# Sheet2.net
KiCad netlist of a schematic drawn in Altium Designer
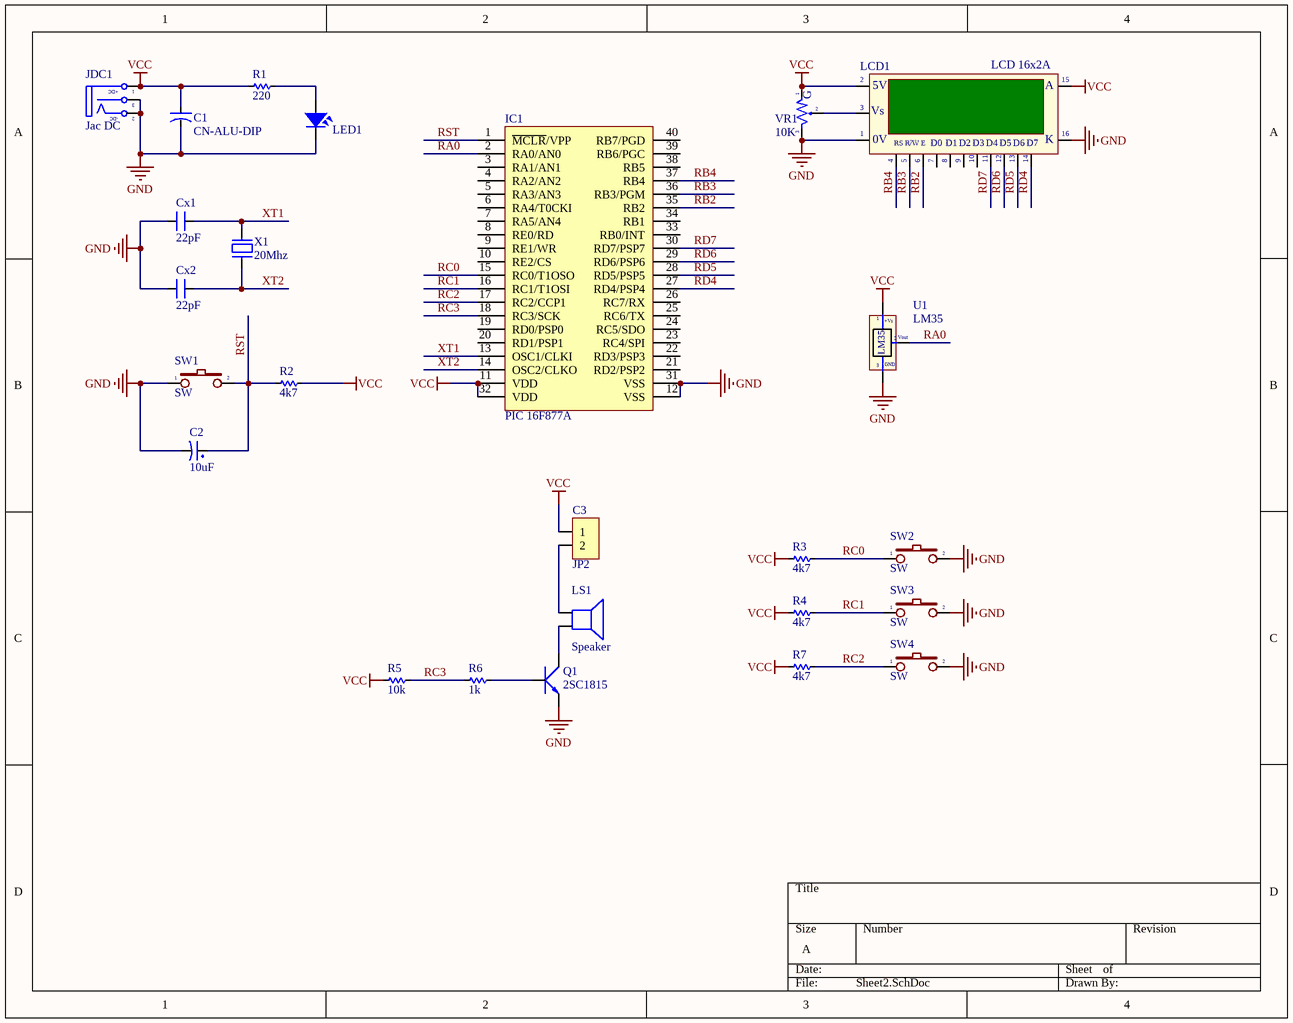
[diagram p0: Sheet2.SchDoc]

(export (version "E")
  (design (tool "Eeschema 10.0.6"))
  (components
    (comp (ref "C1")
      (value "CN-ALU-DIP")
      (footprint "CA-ALU-8")
      (description "Capacitor (Semiconductor SIM Model)")
      (fields (field (name "PUBLISHER") "Altium Limited"))
      (libsource (lib "LIBRARY") (part "CN-ALU-DIP"))
    )
    (comp (ref "C2")
      (value "10uF")
      (footprint "CP1/2")
      (description "Cap P  0,1uF < 22uF , 16 - 50V")
      (libsource (lib "syhaunguyen") (part "CP1"))
    )
    (comp (ref "C3")
      (value "JP2")
      (footprint "JP2-CLOSED")
      (description "WR-PHD 2.54 mm Angled Socket Header")
      (fields
        (field (name "MANUFACTURER") "Würth Elektronik eiSos GmbH")
        (field (name "PARTNO") "613002143121")
        (field (name "CREATED BY") "Karrer Zheng")
      )
      (libsource (lib "LIBRARY") (part "JP2"))
    )
    (comp (ref "Cx1") (value "22pF") (footprint "CN1") (libsource (lib "LIBRARY") (part "CN")))
    (comp (ref "Cx2") (value "22pF") (footprint "CN1") (libsource (lib "LIBRARY") (part "CN")))
    (comp (ref "IC1")
      (value "PIC 16F877A")
      (footprint "DIP40/W0.6")
      (description "8K FLASH, 368B RAM, 256B EFROM")
      (fields (field (name "COPYRIGHT BY") "VanDungEvn"))
      (libsource (lib "LIBRARY") (part "PIC16F877-PU"))
    )
    (comp (ref "JDC1")
      (value "Jac DC")
      (footprint "DC0")
      (description "Jac DC input")
      (libsource (lib "LIBRARY") (part "DCIN"))
    )
    (comp (ref "LCD1")
      (value "LCD 16x2A")
      (footprint "LCD16X2")
      (description "LCD dipslay 16 char, 2 line")
      (libsource (lib "LIBRARY") (part "LCD16x2A"))
    )
    (comp (ref "LED1")
      (value "LED")
      (footprint "LED-5-RED")
      (description "LED Single colour Green and Red")
      (libsource (lib "LIBRARY") (part "LED"))
    )
    (comp (ref "LS1")
      (value "Speaker")
      (footprint "SPEAKER")
      (description "Loudspeaker")
      (fields (field (name "PUBLISHER") "Altium Limited"))
      (libsource (lib "LIBRARY") (part "Speaker"))
    )
    (comp (ref "Q1")
      (value "2SC1815")
      (footprint "TO92-123")
      (description "NPN 600mW, ECB")
      (libsource (lib "LIBRARY") (part "2SC1815"))
    )
    (comp (ref "R1")
      (value "220")
      (footprint "RES-1/4W")
      (description "Res")
      (fields
        (field (name "MANUFACTURER") "Generic Components")
        (field (name "PUBLISHER") "Altium Hobart Technology Centre")
      )
      (libsource (lib "LIBRARY") (part "Res"))
    )
    (comp (ref "R2")
      (value "4k7")
      (footprint "RES-1/4W")
      (description "Res")
      (fields
        (field (name "MANUFACTURER") "Generic Components")
        (field (name "PUBLISHER") "Altium Hobart Technology Centre")
      )
      (libsource (lib "LIBRARY") (part "Res"))
    )
    (comp (ref "R3")
      (value "4k7")
      (footprint "RES-1/4W")
      (description "Res")
      (fields
        (field (name "MANUFACTURER") "Generic Components")
        (field (name "PUBLISHER") "Altium Hobart Technology Centre")
      )
      (libsource (lib "LIBRARY") (part "Res"))
    )
    (comp (ref "R4")
      (value "4k7")
      (footprint "RES-1/4W")
      (description "Res")
      (fields
        (field (name "MANUFACTURER") "Generic Components")
        (field (name "PUBLISHER") "Altium Hobart Technology Centre")
      )
      (libsource (lib "LIBRARY") (part "Res"))
    )
    (comp (ref "R5")
      (value "10k")
      (footprint "RES-SMD-0805")
      (description "Resistor")
      (fields
        (field (name "MANUFACTURER") "Generic Components")
        (field (name "PUBLISHER") "Altium Hobart Technology Centre")
      )
      (libsource (lib "LIBRARY") (part "Res-SMD"))
    )
    (comp (ref "R6")
      (value "1k")
      (footprint "RES-1/4W")
      (description "Res")
      (fields
        (field (name "MANUFACTURER") "Generic Components")
        (field (name "PUBLISHER") "Altium Hobart Technology Centre")
      )
      (libsource (lib "LIBRARY") (part "Res"))
    )
    (comp (ref "R7")
      (value "4k7")
      (footprint "RES-1/4W")
      (description "Res")
      (fields
        (field (name "MANUFACTURER") "Generic Components")
        (field (name "PUBLISHER") "Altium Hobart Technology Centre")
      )
      (libsource (lib "LIBRARY") (part "Res"))
    )
    (comp (ref "SW1")
      (value "SW")
      (footprint "SW2")
      (description "Switch button 2 pin")
      (libsource (lib "syhaunguyen") (part "SW2"))
    )
    (comp (ref "SW2")
      (value "SW")
      (footprint "SW2")
      (description "Switch button 2 pin")
      (libsource (lib "syhaunguyen") (part "SW2"))
    )
    (comp (ref "SW3")
      (value "SW")
      (footprint "SW2")
      (description "Switch button 2 pin")
      (libsource (lib "syhaunguyen") (part "SW2"))
    )
    (comp (ref "SW4")
      (value "SW")
      (footprint "SW2")
      (description "Switch button 2 pin")
      (libsource (lib "syhaunguyen") (part "SW2"))
    )
    (comp (ref "U1")
      (value "LM35")
      (footprint "JP3-C1T")
      (description "Teminal")
      (libsource (lib "LIBRARY") (part "LM35"))
    )
    (comp (ref "VR1")
      (value "10K")
      (footprint "VR-S2")
      (description "Var Resistor")
      (libsource (lib "LIBRARY") (part "VR-S"))
    )
    (comp (ref "X1")
      (value "20Mhz")
      (footprint "XT2")
      (description "Crystal, 32.768 KHz, -40 to 85 degC, 3.2 x 1.5 x 0.9 mm SMD")
      (libsource (lib "LIBRARY") (part "XT2"))
    )
  )
  (nets
    (net (code "1") (name "/RA0") (class "Default")
      (node (ref "IC1") (pin "2") (pinfunction "RA0/AN0_2") (pintype "passive"))
      (node (ref "U1") (pin "2") (pinfunction "Vout_2") (pintype "passive"))
    )
    (net (code "2") (name "/RB2") (class "Default")
      (node (ref "IC1") (pin "35") (pinfunction "RB2_35") (pintype "passive"))
      (node (ref "LCD1") (pin "6") (pinfunction "~{EN}_6") (pintype "passive"))
    )
    (net (code "3") (name "/RB3") (class "Default")
      (node (ref "IC1") (pin "36") (pinfunction "RB3/PGM_36") (pintype "passive"))
      (node (ref "LCD1") (pin "5") (pinfunction "R/~{W}_5") (pintype "passive"))
    )
    (net (code "4") (name "/RB4") (class "Default")
      (node (ref "IC1") (pin "37") (pinfunction "RB4_37") (pintype "passive"))
      (node (ref "LCD1") (pin "4") (pinfunction "RS_4") (pintype "passive"))
    )
    (net (code "5") (name "/RC0") (class "Default")
      (node (ref "IC1") (pin "15") (pinfunction "RC0/T1OSO_15") (pintype "passive"))
      (node (ref "R3") (pin "1") (pinfunction "1_1") (pintype "passive"))
      (node (ref "SW2") (pin "1") (pinfunction "1_1") (pintype "passive"))
    )
    (net (code "6") (name "/RC1") (class "Default")
      (node (ref "IC1") (pin "16") (pinfunction "RC1/T1OSI_16") (pintype "passive"))
      (node (ref "R4") (pin "1") (pinfunction "1_1") (pintype "passive"))
      (node (ref "SW3") (pin "1") (pinfunction "1_1") (pintype "passive"))
    )
    (net (code "7") (name "/RC2") (class "Default")
      (node (ref "IC1") (pin "17") (pinfunction "RC2/CCP1_17") (pintype "passive"))
      (node (ref "R7") (pin "1") (pinfunction "1_1") (pintype "passive"))
      (node (ref "SW4") (pin "1") (pinfunction "1_1") (pintype "passive"))
    )
    (net (code "8") (name "/RC3") (class "Default")
      (node (ref "IC1") (pin "18") (pinfunction "RC3/SCK_18") (pintype "passive"))
      (node (ref "R5") (pin "1") (pinfunction "1_1") (pintype "passive"))
      (node (ref "R6") (pin "2") (pinfunction "2_2") (pintype "passive"))
    )
    (net (code "9") (name "/RD4") (class "Default")
      (node (ref "IC1") (pin "27") (pinfunction "RD4/PSP4_27") (pintype "passive"))
      (node (ref "LCD1") (pin "14") (pinfunction "D7_14") (pintype "passive"))
    )
    (net (code "10") (name "/RD5") (class "Default")
      (node (ref "IC1") (pin "28") (pinfunction "RD5/PSP5_28") (pintype "passive"))
      (node (ref "LCD1") (pin "13") (pinfunction "D6_13") (pintype "passive"))
    )
    (net (code "11") (name "/RD6") (class "Default")
      (node (ref "IC1") (pin "29") (pinfunction "RD6/PSP6_29") (pintype "passive"))
      (node (ref "LCD1") (pin "12") (pinfunction "D5_12") (pintype "passive"))
    )
    (net (code "12") (name "/RD7") (class "Default")
      (node (ref "IC1") (pin "30") (pinfunction "RD7/PSP7_30") (pintype "passive"))
      (node (ref "LCD1") (pin "11") (pinfunction "D4_11") (pintype "passive"))
    )
    (net (code "13") (name "/RST") (class "Default")
      (node (ref "C2") (pin "1") (pinfunction "1_1") (pintype "passive"))
      (node (ref "IC1") (pin "1") (pinfunction "~{MCLR}/VPP_1") (pintype "passive"))
      (node (ref "R2") (pin "2") (pinfunction "2_2") (pintype "passive"))
      (node (ref "SW1") (pin "2") (pinfunction "2_2") (pintype "passive"))
    )
    (net (code "14") (name "/XT1") (class "Default")
      (node (ref "Cx1") (pin "2") (pinfunction "2_2") (pintype "passive"))
      (node (ref "IC1") (pin "13") (pinfunction "OSC1/CLKI_13") (pintype "passive"))
      (node (ref "X1") (pin "2") (pinfunction "2_2") (pintype "passive"))
    )
    (net (code "15") (name "/XT2") (class "Default")
      (node (ref "Cx2") (pin "2") (pinfunction "2_2") (pintype "passive"))
      (node (ref "IC1") (pin "14") (pinfunction "OSC2/CLKO_14") (pintype "passive"))
      (node (ref "X1") (pin "1") (pinfunction "1_1") (pintype "passive"))
    )
    (net (code "16") (name "GND") (class "Default")
      (node (ref "C1") (pin "2") (pinfunction "2_2") (pintype "passive"))
      (node (ref "C2") (pin "2") (pinfunction "2_2") (pintype "passive"))
      (node (ref "Cx1") (pin "1") (pinfunction "1_1") (pintype "passive"))
      (node (ref "Cx2") (pin "1") (pinfunction "1_1") (pintype "passive"))
      (node (ref "IC1") (pin "12") (pinfunction "VSS_12") (pintype "passive"))
      (node (ref "IC1") (pin "31") (pinfunction "VSS_31") (pintype "passive"))
      (node (ref "JDC1") (pin "2") (pinfunction "TN_2") (pintype "passive"))
      (node (ref "JDC1") (pin "3") (pinfunction "S_3") (pintype "power_in"))
      (node (ref "LCD1") (pin "1") (pinfunction "GND_1") (pintype "passive"))
      (node (ref "LCD1") (pin "16") (pinfunction "K_16") (pintype "passive"))
      (node (ref "LED1") (pin "2") (pinfunction "2_2") (pintype "passive"))
      (node (ref "Q1") (pin "1") (pinfunction "E_1") (pintype "passive"))
      (node (ref "SW1") (pin "1") (pinfunction "1_1") (pintype "passive"))
      (node (ref "SW2") (pin "2") (pinfunction "2_2") (pintype "passive"))
      (node (ref "SW3") (pin "2") (pinfunction "2_2") (pintype "passive"))
      (node (ref "SW4") (pin "2") (pinfunction "2_2") (pintype "passive"))
      (node (ref "U1") (pin "3") (pinfunction "-_3") (pintype "passive"))
      (node (ref "VR1") (pin "3") (pinfunction "3_3") (pintype "passive"))
    )
    (net (code "17") (name "Net-(C3-Pad2)") (class "Default")
      (node (ref "C3") (pin "2") (pinfunction "2_2") (pintype "passive"))
      (node (ref "LS1") (pin "1") (pinfunction "1_1") (pintype "passive"))
    )
    (net (code "18") (name "Net-(LCD1-VEE)") (class "Default")
      (node (ref "LCD1") (pin "3") (pinfunction "VEE_3") (pintype "passive"))
      (node (ref "VR1") (pin "2") (pinfunction "2_2") (pintype "passive"))
    )
    (net (code "19") (name "Net-(LED1-Pad1)") (class "Default")
      (node (ref "LED1") (pin "1") (pinfunction "1_1") (pintype "passive"))
      (node (ref "R1") (pin "1") (pinfunction "1_1") (pintype "passive"))
    )
    (net (code "20") (name "Net-(Q1-B)") (class "Default")
      (node (ref "Q1") (pin "3") (pinfunction "B_3") (pintype "passive"))
      (node (ref "R6") (pin "1") (pinfunction "1_1") (pintype "passive"))
    )
    (net (code "21") (name "Net-(Q1-C)") (class "Default")
      (node (ref "LS1") (pin "2") (pinfunction "2_2") (pintype "passive"))
      (node (ref "Q1") (pin "2") (pinfunction "C_2") (pintype "passive"))
    )
    (net (code "22") (name "VCC") (class "Default")
      (node (ref "C1") (pin "1") (pinfunction "1_1") (pintype "passive"))
      (node (ref "C3") (pin "1") (pinfunction "1_1") (pintype "passive"))
      (node (ref "IC1") (pin "11") (pinfunction "VDD_11") (pintype "passive"))
      (node (ref "IC1") (pin "32") (pinfunction "VDD_32") (pintype "passive"))
      (node (ref "JDC1") (pin "1") (pinfunction "T_1") (pintype "passive"))
      (node (ref "LCD1") (pin "15") (pinfunction "A_15") (pintype "passive"))
      (node (ref "LCD1") (pin "2") (pinfunction "VDD_2") (pintype "passive"))
      (node (ref "R1") (pin "2") (pinfunction "2_2") (pintype "passive"))
      (node (ref "R2") (pin "1") (pinfunction "1_1") (pintype "passive"))
      (node (ref "R3") (pin "2") (pinfunction "2_2") (pintype "passive"))
      (node (ref "R4") (pin "2") (pinfunction "2_2") (pintype "passive"))
      (node (ref "R5") (pin "2") (pinfunction "2_2") (pintype "passive"))
      (node (ref "R7") (pin "2") (pinfunction "2_2") (pintype "passive"))
      (node (ref "U1") (pin "1") (pinfunction "+Vs_1") (pintype "passive"))
      (node (ref "VR1") (pin "1") (pinfunction "1_1") (pintype "passive"))
    )
    (net (code "23") (name "unconnected-(IC1-RA1{slash}AN1-Pad3)") (class "Default")
      (node (ref "IC1") (pin "3") (pinfunction "RA1/AN1_3") (pintype "passive"))
    )
    (net (code "24") (name "unconnected-(IC1-RA2{slash}AN2-Pad4)") (class "Default")
      (node (ref "IC1") (pin "4") (pinfunction "RA2/AN2_4") (pintype "passive"))
    )
    (net (code "25") (name "unconnected-(IC1-RA3{slash}AN3-Pad5)") (class "Default")
      (node (ref "IC1") (pin "5") (pinfunction "RA3/AN3_5") (pintype "passive"))
    )
    (net (code "26") (name "unconnected-(IC1-RA4{slash}T0CKI-Pad6)") (class "Default")
      (node (ref "IC1") (pin "6") (pinfunction "RA4/T0CKI_6") (pintype "passive"))
    )
    (net (code "27") (name "unconnected-(IC1-RA5{slash}AN4-Pad7)") (class "Default")
      (node (ref "IC1") (pin "7") (pinfunction "RA5/AN4_7") (pintype "passive"))
    )
    (net (code "28") (name "unconnected-(IC1-RB0{slash}INT-Pad33)") (class "Default")
      (node (ref "IC1") (pin "33") (pinfunction "RB0/INT_33") (pintype "passive"))
    )
    (net (code "29") (name "unconnected-(IC1-RB1-Pad34)") (class "Default")
      (node (ref "IC1") (pin "34") (pinfunction "RB1_34") (pintype "passive"))
    )
    (net (code "30") (name "unconnected-(IC1-RB5-Pad38)") (class "Default")
      (node (ref "IC1") (pin "38") (pinfunction "RB5_38") (pintype "passive"))
    )
    (net (code "31") (name "unconnected-(IC1-RB6{slash}PGC-Pad39)") (class "Default")
      (node (ref "IC1") (pin "39") (pinfunction "RB6/PGC_39") (pintype "passive"))
    )
    (net (code "32") (name "unconnected-(IC1-RB7{slash}PGD-Pad40)") (class "Default")
      (node (ref "IC1") (pin "40") (pinfunction "RB7/PGD_40") (pintype "passive"))
    )
    (net (code "33") (name "unconnected-(IC1-RC4{slash}SPI-Pad23)") (class "Default")
      (node (ref "IC1") (pin "23") (pinfunction "RC4/SPI_23") (pintype "passive"))
    )
    (net (code "34") (name "unconnected-(IC1-RC5{slash}SDO-Pad24)") (class "Default")
      (node (ref "IC1") (pin "24") (pinfunction "RC5/SDO_24") (pintype "passive"))
    )
    (net (code "35") (name "unconnected-(IC1-RC6{slash}TX-Pad25)") (class "Default")
      (node (ref "IC1") (pin "25") (pinfunction "RC6/TX_25") (pintype "passive"))
    )
    (net (code "36") (name "unconnected-(IC1-RC7{slash}RX-Pad26)") (class "Default")
      (node (ref "IC1") (pin "26") (pinfunction "RC7/RX_26") (pintype "passive"))
    )
    (net (code "37") (name "unconnected-(IC1-RD0{slash}PSP0-Pad19)") (class "Default")
      (node (ref "IC1") (pin "19") (pinfunction "RD0/PSP0_19") (pintype "passive"))
    )
    (net (code "38") (name "unconnected-(IC1-RD1{slash}PSP1-Pad20)") (class "Default")
      (node (ref "IC1") (pin "20") (pinfunction "RD1/PSP1_20") (pintype "passive"))
    )
    (net (code "39") (name "unconnected-(IC1-RD2{slash}PSP2-Pad21)") (class "Default")
      (node (ref "IC1") (pin "21") (pinfunction "RD2/PSP2_21") (pintype "passive"))
    )
    (net (code "40") (name "unconnected-(IC1-RD3{slash}PSP3-Pad22)") (class "Default")
      (node (ref "IC1") (pin "22") (pinfunction "RD3/PSP3_22") (pintype "passive"))
    )
    (net (code "41") (name "unconnected-(IC1-RE0{slash}RD-Pad8)") (class "Default")
      (node (ref "IC1") (pin "8") (pinfunction "RE0/RD_8") (pintype "passive"))
    )
    (net (code "42") (name "unconnected-(IC1-RE1{slash}WR-Pad9)") (class "Default")
      (node (ref "IC1") (pin "9") (pinfunction "RE1/WR_9") (pintype "passive"))
    )
    (net (code "43") (name "unconnected-(IC1-RE2{slash}CS-Pad10)") (class "Default")
      (node (ref "IC1") (pin "10") (pinfunction "RE2/CS_10") (pintype "passive"))
    )
    (net (code "44") (name "unconnected-(LCD1-D0-Pad7)") (class "Default")
      (node (ref "LCD1") (pin "7") (pinfunction "D0_7") (pintype "passive"))
    )
    (net (code "45") (name "unconnected-(LCD1-D1-Pad8)") (class "Default")
      (node (ref "LCD1") (pin "8") (pinfunction "D1_8") (pintype "passive"))
    )
    (net (code "46") (name "unconnected-(LCD1-D2-Pad9)") (class "Default")
      (node (ref "LCD1") (pin "9") (pinfunction "D2_9") (pintype "passive"))
    )
    (net (code "47") (name "unconnected-(LCD1-D3-Pad10)") (class "Default")
      (node (ref "LCD1") (pin "10") (pinfunction "D3_10") (pintype "passive"))
    )
  )
)
